# magspoof.net
KiCad netlist of a schematic drawn in EAGLE
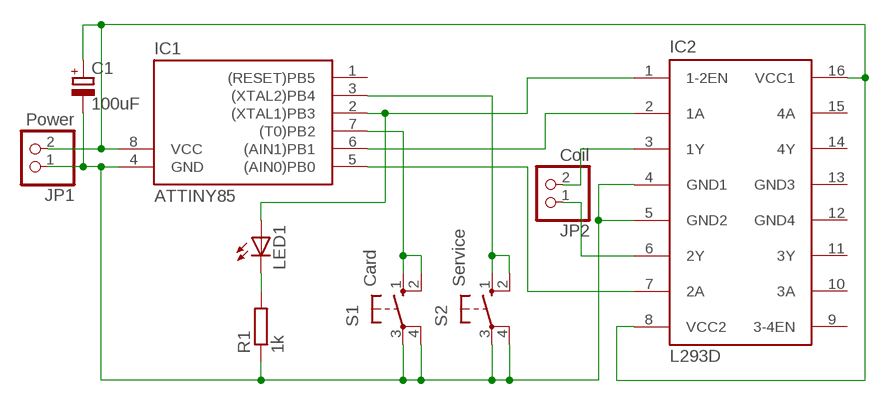
[diagram p0: schematic, sheet 1]

(export (version "E")
  (design (tool "Eeschema 10.0.6"))
  (components
    (comp (ref "C1")
      (value "100uF")
      (footprint "eagle-import:E2,5-6")
      (libsource (lib "eagle-import") (part "CPOL-EUE2.5-6"))
    )
    (comp (ref "IC1")
      (value "ATTINY85")
      (footprint "eagle-import:DIL08")
      (libsource (lib "eagle-import") (part "TINY10P"))
    )
    (comp (ref "IC2")
      (value "L293D")
      (footprint "eagle-import:DIL16")
      (libsource (lib "eagle-import") (part "L293D"))
    )
    (comp (ref "JP1")
      (value "Power")
      (footprint "eagle-import:1X02")
      (libsource (lib "eagle-import") (part "PINHD-1X2"))
    )
    (comp (ref "JP2")
      (value "Coil")
      (footprint "eagle-import:1X02")
      (libsource (lib "eagle-import") (part "PINHD-1X2"))
    )
    (comp (ref "LED1")
      (value "LED3MM")
      (footprint "eagle-import:LED3MM")
      (libsource (lib "eagle-import") (part "LED3MM"))
    )
    (comp (ref "R1")
      (value "1k")
      (footprint "eagle-import:0207_2V")
      (libsource (lib "eagle-import") (part "R-EU_0207/2V"))
    )
    (comp (ref "S1")
      (value "Card")
      (footprint "eagle-import:B3F-10XX")
      (fields (field (name "MPN") "B3F-1000"))
      (libsource (lib "eagle-import") (part "10-XX"))
    )
    (comp (ref "S2")
      (value "Service")
      (footprint "eagle-import:B3F-10XX")
      (fields (field (name "MPN") "B3F-1000"))
      (libsource (lib "eagle-import") (part "10-XX"))
    )
  )
  (nets
    (net (code "1") (name "/GND3") (class "Default")
      (node (ref "IC2") (pin "13") (pinfunction "GND3_13") (pintype "power_in"))
    )
    (net (code "2") (name "/GND4") (class "Default")
      (node (ref "IC2") (pin "12") (pinfunction "GND4_12") (pintype "power_in"))
    )
    (net (code "3") (name "Net-(IC1-(AIN0)PB0)") (class "Default")
      (node (ref "IC1") (pin "5") (pinfunction "(AIN0)PB0_5") (pintype "bidirectional"))
      (node (ref "IC2") (pin "7") (pinfunction "2A_7") (pintype "input"))
    )
    (net (code "4") (name "Net-(IC1-(AIN1)PB1)") (class "Default")
      (node (ref "IC1") (pin "6") (pinfunction "(AIN1)PB1_6") (pintype "bidirectional"))
      (node (ref "IC2") (pin "2") (pinfunction "1A_2") (pintype "input"))
    )
    (net (code "5") (name "Net-(IC1-(T0)PB2)") (class "Default")
      (node (ref "IC1") (pin "7") (pinfunction "(T0)PB2_7") (pintype "bidirectional"))
      (node (ref "S1") (pin "1") (pinfunction "S_1") (pintype "passive"))
      (node (ref "S1") (pin "2") (pinfunction "S1_2") (pintype "passive"))
    )
    (net (code "6") (name "Net-(IC1-(XTAL1)PB3)") (class "Default")
      (node (ref "IC1") (pin "2") (pinfunction "(XTAL1)PB3_2") (pintype "bidirectional"))
      (node (ref "IC2") (pin "1") (pinfunction "1-2EN_1") (pintype "input"))
      (node (ref "LED1") (pin "A") (pinfunction "A_A") (pintype "passive"))
    )
    (net (code "7") (name "Net-(IC1-(XTAL2)PB4)") (class "Default")
      (node (ref "IC1") (pin "3") (pinfunction "(XTAL2)PB4_3") (pintype "bidirectional"))
      (node (ref "S2") (pin "1") (pinfunction "S_1") (pintype "passive"))
      (node (ref "S2") (pin "2") (pinfunction "S1_2") (pintype "passive"))
    )
    (net (code "8") (name "Net-(IC1-GND)") (class "Default")
      (node (ref "C1") (pin "-") (pinfunction "-_-") (pintype "passive"))
      (node (ref "IC1") (pin "4") (pinfunction "GND_4") (pintype "power_in"))
      (node (ref "IC2") (pin "4") (pinfunction "GND1_4") (pintype "power_in"))
      (node (ref "IC2") (pin "5") (pinfunction "GND2_5") (pintype "power_in"))
      (node (ref "JP1") (pin "1") (pinfunction "1_1") (pintype "passive"))
      (node (ref "R1") (pin "1") (pinfunction "1_1") (pintype "passive"))
      (node (ref "S1") (pin "3") (pinfunction "P_3") (pintype "passive"))
      (node (ref "S1") (pin "4") (pinfunction "P1_4") (pintype "passive"))
      (node (ref "S2") (pin "3") (pinfunction "P_3") (pintype "passive"))
      (node (ref "S2") (pin "4") (pinfunction "P1_4") (pintype "passive"))
    )
    (net (code "9") (name "Net-(IC1-VCC)") (class "Default")
      (node (ref "C1") (pin "+") (pinfunction "+_+") (pintype "passive"))
      (node (ref "IC1") (pin "8") (pinfunction "VCC_8") (pintype "power_in"))
      (node (ref "IC2") (pin "16") (pinfunction "VCC1_16") (pintype "power_in"))
      (node (ref "IC2") (pin "8") (pinfunction "VCC2_8") (pintype "power_in"))
      (node (ref "JP1") (pin "2") (pinfunction "2_2") (pintype "passive"))
    )
    (net (code "10") (name "Net-(IC2-1Y)") (class "Default")
      (node (ref "IC2") (pin "3") (pinfunction "1Y_3") (pintype "output"))
      (node (ref "JP2") (pin "2") (pinfunction "2_2") (pintype "passive"))
    )
    (net (code "11") (name "Net-(IC2-2Y)") (class "Default")
      (node (ref "IC2") (pin "6") (pinfunction "2Y_6") (pintype "output"))
      (node (ref "JP2") (pin "1") (pinfunction "1_1") (pintype "passive"))
    )
    (net (code "12") (name "Net-(LED1-C)") (class "Default")
      (node (ref "LED1") (pin "K") (pinfunction "C_K") (pintype "passive"))
      (node (ref "R1") (pin "2") (pinfunction "2_2") (pintype "passive"))
    )
    (net (code "13") (name "unconnected-(IC1-(RESET)PB5-Pad1)") (class "Default")
      (node (ref "IC1") (pin "1") (pinfunction "(RESET)PB5_1") (pintype "bidirectional"))
    )
    (net (code "14") (name "unconnected-(IC2-3-4EN-Pad9)") (class "Default")
      (node (ref "IC2") (pin "9") (pinfunction "3-4EN_9") (pintype "input"))
    )
    (net (code "15") (name "unconnected-(IC2-3A-Pad10)") (class "Default")
      (node (ref "IC2") (pin "10") (pinfunction "3A_10") (pintype "input"))
    )
    (net (code "16") (name "unconnected-(IC2-3Y-Pad11)") (class "Default")
      (node (ref "IC2") (pin "11") (pinfunction "3Y_11") (pintype "output"))
    )
    (net (code "17") (name "unconnected-(IC2-4A-Pad15)") (class "Default")
      (node (ref "IC2") (pin "15") (pinfunction "4A_15") (pintype "input"))
    )
    (net (code "18") (name "unconnected-(IC2-4Y-Pad14)") (class "Default")
      (node (ref "IC2") (pin "14") (pinfunction "4Y_14") (pintype "output"))
    )
  )
)
